# electric-skateboard-v2.net
KiCad netlist of a schematic drawn in EAGLE
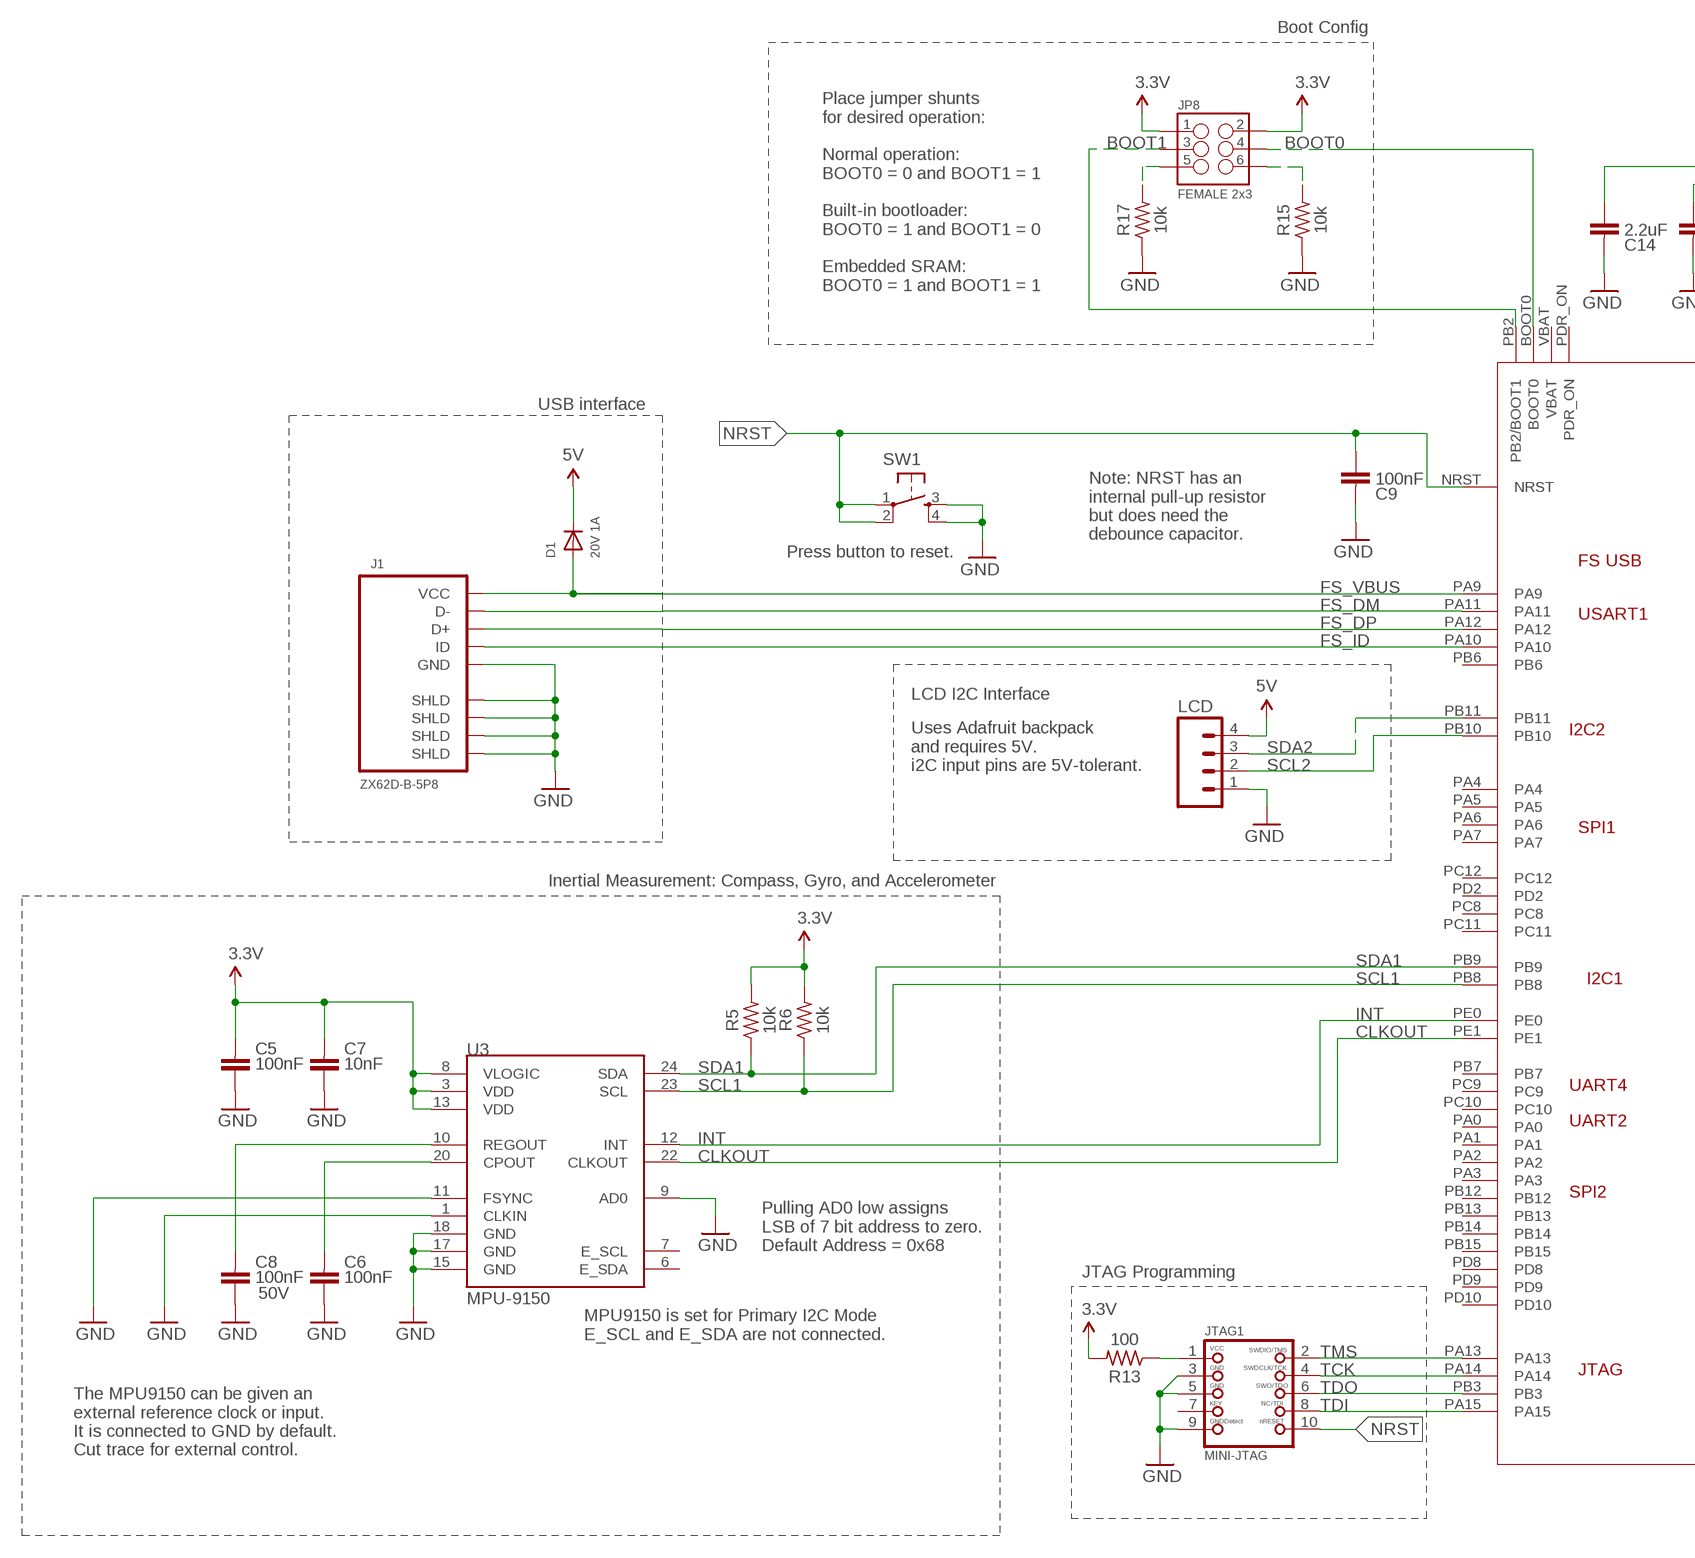
[diagram p0: schematic, sheet 1, part 1 of 2]
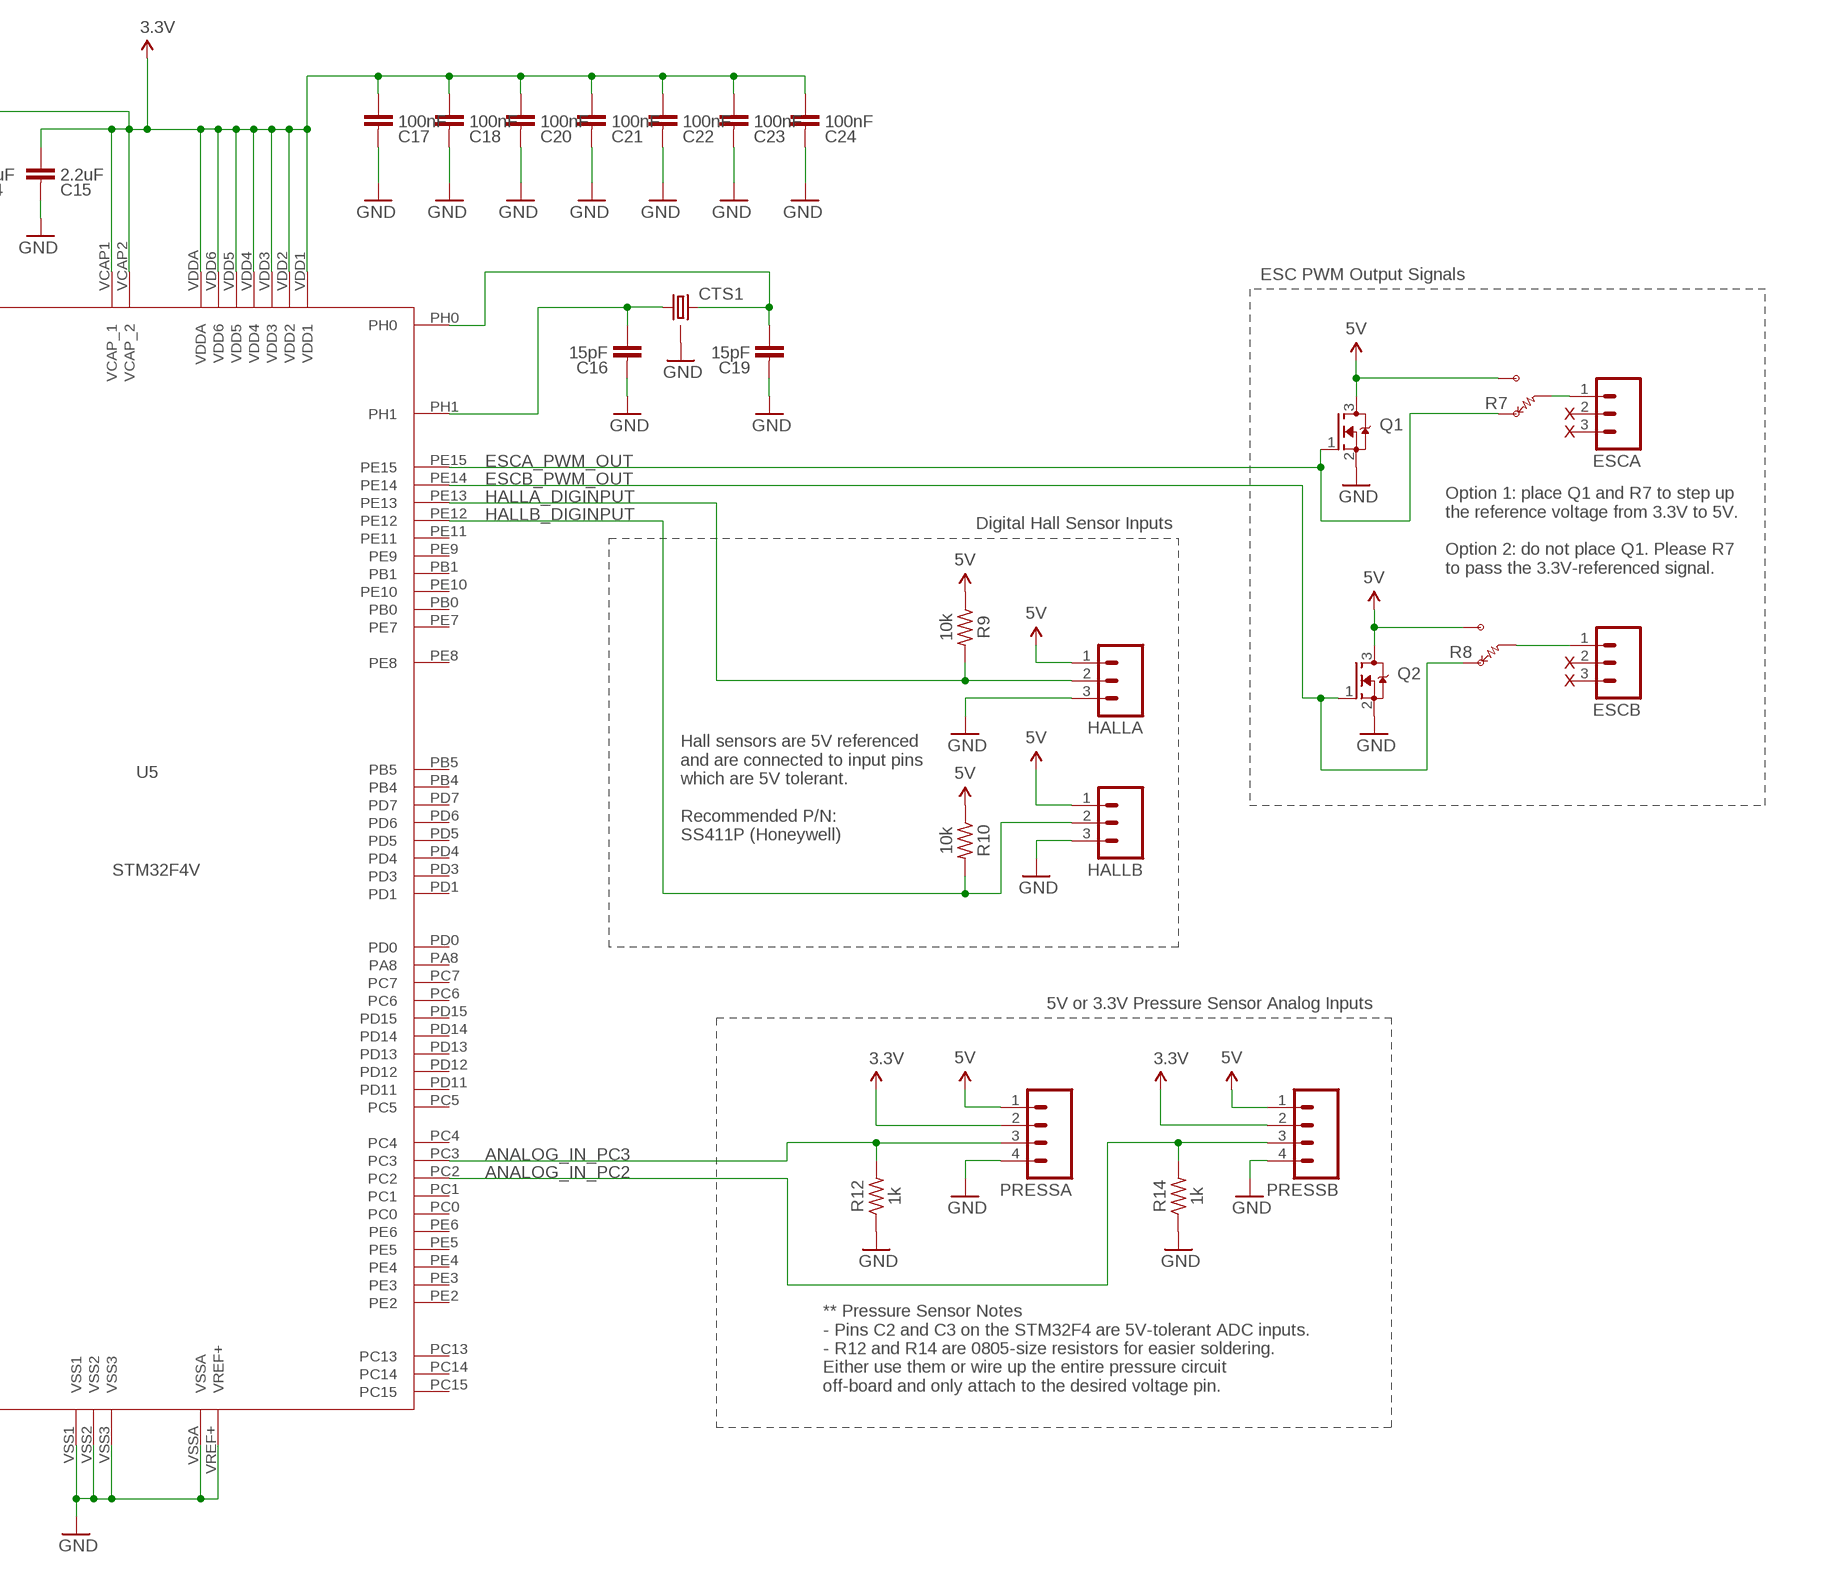
[diagram p1: schematic, sheet 1, part 2 of 2]
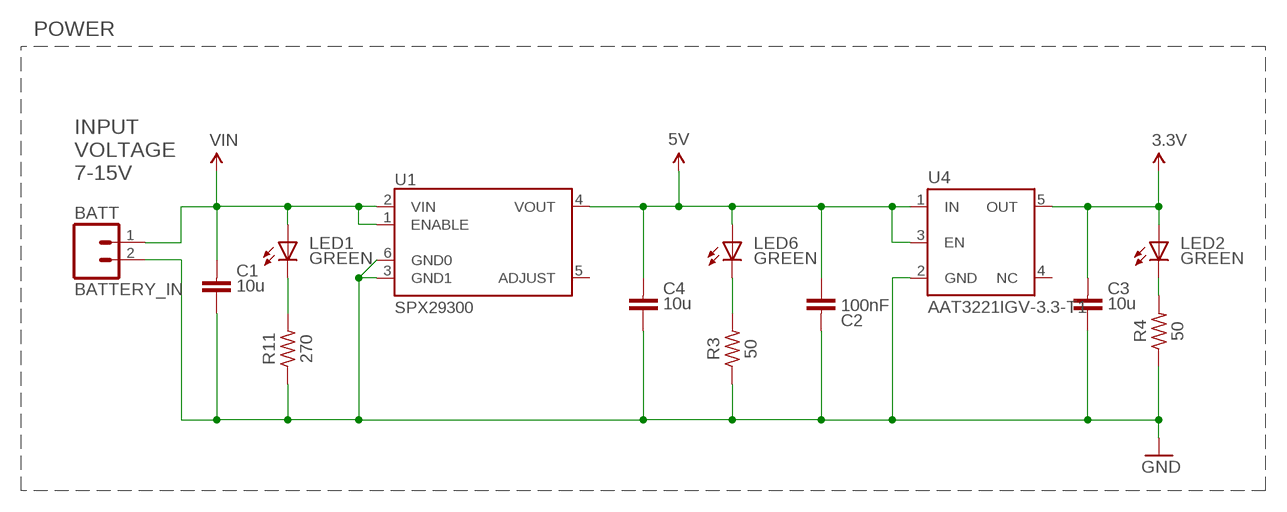
[diagram p2: schematic, sheet 2]

(export (version "E")
  (design (tool "Eeschema 10.0.6"))
  (components
    (comp (ref "BATTERY_IN")
      (value "BATT")
      (footprint "eagle-import:SCREWTERMINAL-5MM-2")
      (libsource (lib "eagle-import") (part "M025MM"))
    )
    (comp (ref "C1")
      (value "10u")
      (footprint "eagle-import:RLC-1210")
      (libsource (lib "eagle-import") (part "CAP-1210"))
    )
    (comp (ref "C2")
      (value "100nF")
      (footprint "eagle-import:RLC-0402")
      (libsource (lib "eagle-import") (part "CAP-0402"))
    )
    (comp (ref "C3")
      (value "10u")
      (footprint "eagle-import:RLC-1210")
      (libsource (lib "eagle-import") (part "CAP-1210"))
    )
    (comp (ref "C4")
      (value "10u")
      (footprint "eagle-import:RLC-1210")
      (libsource (lib "eagle-import") (part "CAP-1210"))
    )
    (comp (ref "LED1")
      (value "GREEN")
      (footprint "eagle-import:LED0603")
      (libsource (lib "eagle-import") (part "BG1111C"))
    )
    (comp (ref "LED2")
      (value "GREEN")
      (footprint "eagle-import:LED0603")
      (libsource (lib "eagle-import") (part "BG1111C"))
    )
    (comp (ref "LED6")
      (value "GREEN")
      (footprint "eagle-import:LED0603")
      (libsource (lib "eagle-import") (part "BG1111C"))
    )
    (comp (ref "R3")
      (value "50")
      (footprint "eagle-import:RLC-0402")
      (libsource (lib "eagle-import") (part "RES-0402"))
    )
    (comp (ref "R4")
      (value "50")
      (footprint "eagle-import:RLC-0402")
      (libsource (lib "eagle-import") (part "RES-0402"))
    )
    (comp (ref "R11")
      (value "270")
      (footprint "eagle-import:RLC-0402")
      (libsource (lib "eagle-import") (part "RES-0402"))
    )
    (comp (ref "U1")
      (value "SPX29300")
      (footprint "eagle-import:TO263-5")
      (libsource (lib "eagle-import") (part "VREG_TO263-5"))
    )
    (comp (ref "U4")
      (value "AAT3221IGV-3.3-T1")
      (footprint "eagle-import:SOT23-5")
      (libsource (lib "eagle-import") (part "INVERTER_SOT23-5"))
    )
    (comp (ref "C5")
      (value "100nF")
      (footprint "eagle-import:RLC-0402")
      (libsource (lib "eagle-import") (part "CAP-0402"))
    )
    (comp (ref "C6")
      (value "100nF")
      (footprint "eagle-import:RLC-0402")
      (libsource (lib "eagle-import") (part "CAP-0402"))
    )
    (comp (ref "C7")
      (value "10nF")
      (footprint "eagle-import:RLC-0402")
      (libsource (lib "eagle-import") (part "CAP-0402"))
    )
    (comp (ref "C8")
      (value "100nF")
      (footprint "eagle-import:RLC-0402")
      (libsource (lib "eagle-import") (part "CAP-0402"))
    )
    (comp (ref "C9")
      (value "100nF")
      (footprint "eagle-import:RLC-0402")
      (libsource (lib "eagle-import") (part "CAP-0402"))
    )
    (comp (ref "C14")
      (value "2.2uF")
      (footprint "eagle-import:RLC-0805")
      (libsource (lib "eagle-import") (part "CAP-0805"))
    )
    (comp (ref "C15")
      (value "2.2uF")
      (footprint "eagle-import:RLC-0805")
      (libsource (lib "eagle-import") (part "CAP-0805"))
    )
    (comp (ref "C16")
      (value "15pF")
      (footprint "eagle-import:RLC-0402")
      (libsource (lib "eagle-import") (part "CAP-0402"))
    )
    (comp (ref "C17")
      (value "100nF")
      (footprint "eagle-import:RLC-0402")
      (libsource (lib "eagle-import") (part "CAP-0402"))
    )
    (comp (ref "C18")
      (value "100nF")
      (footprint "eagle-import:RLC-0402")
      (libsource (lib "eagle-import") (part "CAP-0402"))
    )
    (comp (ref "C19")
      (value "15pF")
      (footprint "eagle-import:RLC-0402")
      (libsource (lib "eagle-import") (part "CAP-0402"))
    )
    (comp (ref "C20")
      (value "100nF")
      (footprint "eagle-import:RLC-0402")
      (libsource (lib "eagle-import") (part "CAP-0402"))
    )
    (comp (ref "C21")
      (value "100nF")
      (footprint "eagle-import:RLC-0402")
      (libsource (lib "eagle-import") (part "CAP-0402"))
    )
    (comp (ref "C22")
      (value "100nF")
      (footprint "eagle-import:RLC-0402")
      (libsource (lib "eagle-import") (part "CAP-0402"))
    )
    (comp (ref "C23")
      (value "100nF")
      (footprint "eagle-import:RLC-0402")
      (libsource (lib "eagle-import") (part "CAP-0402"))
    )
    (comp (ref "C24")
      (value "100nF")
      (footprint "eagle-import:RLC-0402")
      (libsource (lib "eagle-import") (part "CAP-0402"))
    )
    (comp (ref "CTS1")
      (value "CRYSTALCTS406")
      (footprint "eagle-import:CTS406")
      (libsource (lib "eagle-import") (part "CRYSTALCTS406"))
    )
    (comp (ref "D1")
      (value "20V 1A")
      (footprint "eagle-import:SMADIODE")
      (libsource (lib "eagle-import") (part "DIODESMA"))
    )
    (comp (ref "ESCA")
      (value "M03LOCK_LONGPADS")
      (footprint "eagle-import:1X03_LOCK_LONGPADS")
      (libsource (lib "eagle-import") (part "M03LOCK_LONGPADS"))
    )
    (comp (ref "ESCB")
      (value "M03LOCK_LONGPADS")
      (footprint "eagle-import:1X03_LOCK_LONGPADS")
      (libsource (lib "eagle-import") (part "M03LOCK_LONGPADS"))
    )
    (comp (ref "HALLA")
      (value "M03LOCK_LONGPADS")
      (footprint "eagle-import:1X03_LOCK_LONGPADS")
      (libsource (lib "eagle-import") (part "M03LOCK_LONGPADS"))
    )
    (comp (ref "HALLB")
      (value "M03LOCK_LONGPADS")
      (footprint "eagle-import:1X03_LOCK_LONGPADS")
      (libsource (lib "eagle-import") (part "M03LOCK_LONGPADS"))
    )
    (comp (ref "J1")
      (value "ZX62D-B-5P8")
      (footprint "eagle-import:ZX62D-B-5P8")
      (libsource (lib "eagle-import") (part "ZX62D-B-5P8"))
    )
    (comp (ref "JP8")
      (value "FEMALE 2x3")
      (footprint "eagle-import:2X3")
      (libsource (lib "eagle-import") (part "M03X2FEMALE"))
    )
    (comp (ref "JTAG1")
      (value "MINI-JTAG")
      (footprint "eagle-import:MICROBUILDER_2X05_1.27MM_SMT")
      (libsource (lib "eagle-import") (part "MICROBUILDER_JTAG-CORTEXM3"))
    )
    (comp (ref "LCD")
      (value "M04SCREW_LOCK")
      (footprint "eagle-import:SCREWTERMINAL-3.5MM-4_LOCK")
      (libsource (lib "eagle-import") (part "M04SCREW_LOCK"))
    )
    (comp (ref "PRESSA")
      (value "M04LOCK_LONGPADS")
      (footprint "eagle-import:1X04_LOCK_LONGPADS")
      (libsource (lib "eagle-import") (part "M04LOCK_LONGPADS"))
    )
    (comp (ref "PRESSB")
      (value "M04LOCK_LONGPADS")
      (footprint "eagle-import:1X04_LOCK_LONGPADS")
      (libsource (lib "eagle-import") (part "M04LOCK_LONGPADS"))
    )
    (comp (ref "Q1")
      (value "NTR4501N-D")
      (footprint "eagle-import:SOT-23")
      (libsource (lib "eagle-import") (part "NTR4501N-D"))
    )
    (comp (ref "Q2")
      (value "NTR4501N-D")
      (footprint "eagle-import:SOT-23")
      (libsource (lib "eagle-import") (part "NTR4501N-D"))
    )
    (comp (ref "R5")
      (value "10k")
      (footprint "eagle-import:RLC-0402")
      (libsource (lib "eagle-import") (part "RES-0402"))
    )
    (comp (ref "R6")
      (value "10k")
      (footprint "eagle-import:RLC-0402")
      (libsource (lib "eagle-import") (part "RES-0402"))
    )
    (comp (ref "R7")
      (value "RES-OPTION")
      (footprint "eagle-import:CAP-OPTION")
      (libsource (lib "eagle-import") (part "RES-OPTION"))
    )
    (comp (ref "R8")
      (value "RES-OPTION")
      (footprint "eagle-import:CAP-OPTION")
      (libsource (lib "eagle-import") (part "RES-OPTION"))
    )
    (comp (ref "R9")
      (value "10k")
      (footprint "eagle-import:RLC-0402")
      (libsource (lib "eagle-import") (part "RES-0402"))
    )
    (comp (ref "R10")
      (value "10k")
      (footprint "eagle-import:RLC-0402")
      (libsource (lib "eagle-import") (part "RES-0402"))
    )
    (comp (ref "R12")
      (value "1k")
      (footprint "eagle-import:RLC-0402")
      (libsource (lib "eagle-import") (part "RES-0402"))
    )
    (comp (ref "R13")
      (value "100")
      (footprint "eagle-import:RLC-0402")
      (libsource (lib "eagle-import") (part "RES-0402"))
    )
    (comp (ref "R14")
      (value "1k")
      (footprint "eagle-import:RLC-0402")
      (libsource (lib "eagle-import") (part "RES-0402"))
    )
    (comp (ref "R15")
      (value "10k")
      (footprint "eagle-import:RLC-0402")
      (libsource (lib "eagle-import") (part "RES-0402"))
    )
    (comp (ref "R17")
      (value "10k")
      (footprint "eagle-import:RLC-0402")
      (libsource (lib "eagle-import") (part "RES-0402"))
    )
    (comp (ref "SW1")
      (value "TACTILE-SWITCH-PTH")
      (footprint "eagle-import:TAC-SWITCH-PTH")
      (libsource (lib "eagle-import") (part "TACTILE-SWITCH-PTH"))
    )
    (comp (ref "U3")
      (value "MPU-9150")
      (footprint "eagle-import:QFN-24-NP")
      (libsource (lib "eagle-import") (part "MPU-9150QFN-24-NP"))
    )
    (comp (ref "U5")
      (value "STM32F4V")
      (footprint "eagle-import:STM32F4_LQFP100")
      (libsource (lib "eagle-import") (part "STM32F4_STM32F4V_100PIN_FOXCAR"))
    )
  )
  (nets
    (net (code "1") (name "3.3V") (class "Default")
      (node (ref "C14") (pin "2") (pinfunction "2_2") (pintype "passive"))
      (node (ref "C15") (pin "2") (pinfunction "2_2") (pintype "passive"))
      (node (ref "C17") (pin "2") (pinfunction "2_2") (pintype "passive"))
      (node (ref "C18") (pin "2") (pinfunction "2_2") (pintype "passive"))
      (node (ref "C20") (pin "2") (pinfunction "2_2") (pintype "passive"))
      (node (ref "C21") (pin "2") (pinfunction "2_2") (pintype "passive"))
      (node (ref "C22") (pin "2") (pinfunction "2_2") (pintype "passive"))
      (node (ref "C23") (pin "2") (pinfunction "2_2") (pintype "passive"))
      (node (ref "C24") (pin "2") (pinfunction "2_2") (pintype "passive"))
      (node (ref "C3") (pin "1") (pinfunction "1_1") (pintype "passive"))
      (node (ref "C5") (pin "1") (pinfunction "1_1") (pintype "passive"))
      (node (ref "C7") (pin "1") (pinfunction "1_1") (pintype "passive"))
      (node (ref "JP8") (pin "1") (pinfunction "1_1") (pintype "bidirectional"))
      (node (ref "JP8") (pin "2") (pinfunction "2_2") (pintype "bidirectional"))
      (node (ref "LED2") (pin "A") (pinfunction "A_A") (pintype "passive"))
      (node (ref "PRESSA") (pin "2") (pinfunction "2_2") (pintype "passive"))
      (node (ref "PRESSB") (pin "2") (pinfunction "2_2") (pintype "passive"))
      (node (ref "R13") (pin "2") (pinfunction "2_2") (pintype "passive"))
      (node (ref "R5") (pin "2") (pinfunction "2_2") (pintype "passive"))
      (node (ref "R6") (pin "2") (pinfunction "2_2") (pintype "passive"))
      (node (ref "U3") (pin "13") (pinfunction "VDD_13") (pintype "bidirectional"))
      (node (ref "U3") (pin "3") (pinfunction "VDD_3") (pintype "bidirectional"))
      (node (ref "U3") (pin "8") (pinfunction "VLOGIC_8") (pintype "bidirectional"))
      (node (ref "U4") (pin "5") (pinfunction "OUT_5") (pintype "bidirectional"))
      (node (ref "U5") (pin "VCAP1") (pinfunction "VCAP_1_VCAP1") (pintype "bidirectional"))
      (node (ref "U5") (pin "VCAP2") (pinfunction "VCAP_2_VCAP2") (pintype "bidirectional"))
      (node (ref "U5") (pin "VDD1") (pinfunction "VDD1_VDD1") (pintype "bidirectional"))
      (node (ref "U5") (pin "VDD2") (pinfunction "VDD2_VDD2") (pintype "bidirectional"))
      (node (ref "U5") (pin "VDD3") (pinfunction "VDD3_VDD3") (pintype "bidirectional"))
      (node (ref "U5") (pin "VDD4") (pinfunction "VDD4_VDD4") (pintype "bidirectional"))
      (node (ref "U5") (pin "VDD5") (pinfunction "VDD5_VDD5") (pintype "bidirectional"))
      (node (ref "U5") (pin "VDD6") (pinfunction "VDD6_VDD6") (pintype "bidirectional"))
      (node (ref "U5") (pin "VDDA") (pinfunction "VDDA_VDDA") (pintype "bidirectional"))
    )
    (net (code "2") (name "5V") (class "Default")
      (node (ref "C2") (pin "2") (pinfunction "2_2") (pintype "passive"))
      (node (ref "C4") (pin "1") (pinfunction "1_1") (pintype "passive"))
      (node (ref "D1") (pin "C") (pinfunction "C_C") (pintype "passive"))
      (node (ref "HALLA") (pin "1") (pinfunction "1_1") (pintype "passive"))
      (node (ref "HALLB") (pin "1") (pinfunction "1_1") (pintype "passive"))
      (node (ref "LCD") (pin "4") (pinfunction "4_4") (pintype "passive"))
      (node (ref "LED6") (pin "A") (pinfunction "A_A") (pintype "passive"))
      (node (ref "PRESSA") (pin "1") (pinfunction "1_1") (pintype "passive"))
      (node (ref "PRESSB") (pin "1") (pinfunction "1_1") (pintype "passive"))
      (node (ref "Q1") (pin "3") (pinfunction "D_3") (pintype "bidirectional"))
      (node (ref "Q2") (pin "3") (pinfunction "D_3") (pintype "bidirectional"))
      (node (ref "R10") (pin "1") (pinfunction "1_1") (pintype "passive"))
      (node (ref "R7") (pin "3") (pinfunction "3_3") (pintype "passive"))
      (node (ref "R8") (pin "3") (pinfunction "3_3") (pintype "passive"))
      (node (ref "R9") (pin "1") (pinfunction "1_1") (pintype "passive"))
      (node (ref "U1") (pin "4") (pinfunction "VOUT_4") (pintype "bidirectional"))
      (node (ref "U4") (pin "1") (pinfunction "IN_1") (pintype "bidirectional"))
      (node (ref "U4") (pin "3") (pinfunction "EN_3") (pintype "bidirectional"))
    )
    (net (code "3") (name "ANALOG_IN_PC2") (class "Default")
      (node (ref "PRESSB") (pin "3") (pinfunction "3_3") (pintype "passive"))
      (node (ref "R14") (pin "2") (pinfunction "2_2") (pintype "passive"))
      (node (ref "U5") (pin "PC2") (pinfunction "PC2_PC2") (pintype "bidirectional"))
    )
    (net (code "4") (name "ANALOG_IN_PC3") (class "Default")
      (node (ref "PRESSA") (pin "3") (pinfunction "3_3") (pintype "passive"))
      (node (ref "R12") (pin "2") (pinfunction "2_2") (pintype "passive"))
      (node (ref "U5") (pin "PC3") (pinfunction "PC3_PC3") (pintype "bidirectional"))
    )
    (net (code "5") (name "BOOT0") (class "Default")
      (node (ref "JP8") (pin "4") (pinfunction "4_4") (pintype "bidirectional"))
      (node (ref "U5") (pin "BOOT0") (pinfunction "BOOT0_BOOT0") (pintype "bidirectional"))
    )
    (net (code "6") (name "BOOT1") (class "Default")
      (node (ref "JP8") (pin "3") (pinfunction "3_3") (pintype "bidirectional"))
      (node (ref "U5") (pin "PB2") (pinfunction "PB2/BOOT1_PB2") (pintype "bidirectional"))
    )
    (net (code "7") (name "CLKOUT") (class "Default")
      (node (ref "U3") (pin "22") (pinfunction "CLKOUT_22") (pintype "bidirectional"))
      (node (ref "U5") (pin "PE1") (pinfunction "PE1_PE1") (pintype "bidirectional"))
    )
    (net (code "8") (name "ESCA_PWM_OUT") (class "Default")
      (node (ref "Q1") (pin "1") (pinfunction "G_1") (pintype "bidirectional"))
      (node (ref "R7") (pin "1") (pinfunction "1_1") (pintype "passive"))
      (node (ref "U5") (pin "PE15") (pinfunction "PE15_PE15") (pintype "bidirectional"))
    )
    (net (code "9") (name "ESCB_PWM_OUT") (class "Default")
      (node (ref "Q2") (pin "1") (pinfunction "G_1") (pintype "bidirectional"))
      (node (ref "R8") (pin "1") (pinfunction "1_1") (pintype "passive"))
      (node (ref "U5") (pin "PE14") (pinfunction "PE14_PE14") (pintype "bidirectional"))
    )
    (net (code "10") (name "FS_DM") (class "Default")
      (node (ref "J1") (pin "P2") (pinfunction "D-_P2") (pintype "bidirectional"))
      (node (ref "U5") (pin "PA11") (pinfunction "PA11_PA11") (pintype "bidirectional"))
    )
    (net (code "11") (name "FS_DP") (class "Default")
      (node (ref "J1") (pin "P3") (pinfunction "D+_P3") (pintype "bidirectional"))
      (node (ref "U5") (pin "PA12") (pinfunction "PA12_PA12") (pintype "bidirectional"))
    )
    (net (code "12") (name "FS_ID") (class "Default")
      (node (ref "J1") (pin "P4") (pinfunction "ID_P4") (pintype "bidirectional"))
      (node (ref "U5") (pin "PA10") (pinfunction "PA10_PA10") (pintype "bidirectional"))
    )
    (net (code "13") (name "FS_VBUS") (class "Default")
      (node (ref "D1") (pin "A") (pinfunction "A_A") (pintype "passive"))
      (node (ref "J1") (pin "P1") (pinfunction "VCC_P1") (pintype "power_in"))
      (node (ref "U5") (pin "PA9") (pinfunction "PA9_PA9") (pintype "bidirectional"))
    )
    (net (code "14") (name "GND") (class "Default")
      (node (ref "BATTERY_IN") (pin "2") (pinfunction "2_2") (pintype "passive"))
      (node (ref "C1") (pin "2") (pinfunction "2_2") (pintype "passive"))
      (node (ref "C14") (pin "1") (pinfunction "1_1") (pintype "passive"))
      (node (ref "C15") (pin "1") (pinfunction "1_1") (pintype "passive"))
      (node (ref "C16") (pin "1") (pinfunction "1_1") (pintype "passive"))
      (node (ref "C17") (pin "1") (pinfunction "1_1") (pintype "passive"))
      (node (ref "C18") (pin "1") (pinfunction "1_1") (pintype "passive"))
      (node (ref "C19") (pin "1") (pinfunction "1_1") (pintype "passive"))
      (node (ref "C2") (pin "1") (pinfunction "1_1") (pintype "passive"))
      (node (ref "C20") (pin "1") (pinfunction "1_1") (pintype "passive"))
      (node (ref "C21") (pin "1") (pinfunction "1_1") (pintype "passive"))
      (node (ref "C22") (pin "1") (pinfunction "1_1") (pintype "passive"))
      (node (ref "C23") (pin "1") (pinfunction "1_1") (pintype "passive"))
      (node (ref "C24") (pin "1") (pinfunction "1_1") (pintype "passive"))
      (node (ref "C3") (pin "2") (pinfunction "2_2") (pintype "passive"))
      (node (ref "C4") (pin "2") (pinfunction "2_2") (pintype "passive"))
      (node (ref "C5") (pin "2") (pinfunction "2_2") (pintype "passive"))
      (node (ref "C6") (pin "2") (pinfunction "2_2") (pintype "passive"))
      (node (ref "C7") (pin "2") (pinfunction "2_2") (pintype "passive"))
      (node (ref "C8") (pin "2") (pinfunction "2_2") (pintype "passive"))
      (node (ref "C9") (pin "1") (pinfunction "1_1") (pintype "passive"))
      (node (ref "CTS1") (pin "2") (pinfunction "GND_2") (pintype "power_in"))
      (node (ref "CTS1") (pin "4") (pinfunction "GND_4") (pintype "power_in"))
      (node (ref "HALLA") (pin "3") (pinfunction "3_3") (pintype "passive"))
      (node (ref "HALLB") (pin "3") (pinfunction "3_3") (pintype "passive"))
      (node (ref "J1") (pin "P$1") (pinfunction "SHLD_P$1") (pintype "power_in"))
      (node (ref "J1") (pin "P$2") (pinfunction "SHLD_P$2") (pintype "power_in"))
      (node (ref "J1") (pin "P$3") (pinfunction "SHLD_P$3") (pintype "power_in"))
      (node (ref "J1") (pin "P$4") (pinfunction "SHLD_P$4") (pintype "power_in"))
      (node (ref "J1") (pin "P5") (pinfunction "GND_P5") (pintype "power_in"))
      (node (ref "JTAG1") (pin "3") (pinfunction "3_3") (pintype "passive"))
      (node (ref "JTAG1") (pin "5") (pinfunction "5_5") (pintype "passive"))
      (node (ref "JTAG1") (pin "9") (pinfunction "9_9") (pintype "passive"))
      (node (ref "LCD") (pin "1") (pinfunction "1_1") (pintype "passive"))
      (node (ref "PRESSA") (pin "4") (pinfunction "4_4") (pintype "passive"))
      (node (ref "PRESSB") (pin "4") (pinfunction "4_4") (pintype "passive"))
      (node (ref "Q1") (pin "2") (pinfunction "S_2") (pintype "bidirectional"))
      (node (ref "Q2") (pin "2") (pinfunction "S_2") (pintype "bidirectional"))
      (node (ref "R11") (pin "1") (pinfunction "1_1") (pintype "passive"))
      (node (ref "R12") (pin "1") (pinfunction "1_1") (pintype "passive"))
      (node (ref "R14") (pin "1") (pinfunction "1_1") (pintype "passive"))
      (node (ref "R15") (pin "1") (pinfunction "1_1") (pintype "passive"))
      (node (ref "R17") (pin "1") (pinfunction "1_1") (pintype "passive"))
      (node (ref "R3") (pin "1") (pinfunction "1_1") (pintype "passive"))
      (node (ref "R4") (pin "1") (pinfunction "1_1") (pintype "passive"))
      (node (ref "SW1") (pin "3") (pinfunction "3_3") (pintype "passive"))
      (node (ref "SW1") (pin "4") (pinfunction "4_4") (pintype "passive"))
      (node (ref "U1") (pin "3") (pinfunction "GND1_3") (pintype "bidirectional"))
      (node (ref "U1") (pin "6") (pinfunction "GND0_6") (pintype "bidirectional"))
      (node (ref "U3") (pin "1") (pinfunction "CLKIN_1") (pintype "bidirectional"))
      (node (ref "U3") (pin "11") (pinfunction "FSYNC_11") (pintype "bidirectional"))
      (node (ref "U3") (pin "15") (pinfunction "GND_15") (pintype "bidirectional"))
      (node (ref "U3") (pin "17") (pinfunction "GND_17") (pintype "bidirectional"))
      (node (ref "U3") (pin "18") (pinfunction "GND_18") (pintype "bidirectional"))
      (node (ref "U3") (pin "9") (pinfunction "AD0_9") (pintype "bidirectional"))
      (node (ref "U4") (pin "2") (pinfunction "GND_2") (pintype "bidirectional"))
      (node (ref "U5") (pin "VREF+") (pinfunction "VREF+_VREF+") (pintype "bidirectional"))
      (node (ref "U5") (pin "VSS1") (pinfunction "VSS1_VSS1") (pintype "bidirectional"))
      (node (ref "U5") (pin "VSS2") (pinfunction "VSS2_VSS2") (pintype "bidirectional"))
      (node (ref "U5") (pin "VSS3") (pinfunction "VSS3_VSS3") (pintype "bidirectional"))
      (node (ref "U5") (pin "VSSA") (pinfunction "VSSA_VSSA") (pintype "bidirectional"))
    )
    (net (code "15") (name "HALLA_DIGINPUT") (class "Default")
      (node (ref "HALLA") (pin "2") (pinfunction "2_2") (pintype "passive"))
      (node (ref "R9") (pin "2") (pinfunction "2_2") (pintype "passive"))
      (node (ref "U5") (pin "PE13") (pinfunction "PE13_PE13") (pintype "bidirectional"))
    )
    (net (code "16") (name "HALLB_DIGINPUT") (class "Default")
      (node (ref "HALLB") (pin "2") (pinfunction "2_2") (pintype "passive"))
      (node (ref "R10") (pin "2") (pinfunction "2_2") (pintype "passive"))
      (node (ref "U5") (pin "PE12") (pinfunction "PE12_PE12") (pintype "bidirectional"))
    )
    (net (code "17") (name "INT") (class "Default")
      (node (ref "U3") (pin "12") (pinfunction "INT_12") (pintype "bidirectional"))
      (node (ref "U5") (pin "PE0") (pinfunction "PE0_PE0") (pintype "bidirectional"))
    )
    (net (code "18") (name "NRST") (class "Default")
      (node (ref "C9") (pin "2") (pinfunction "2_2") (pintype "passive"))
      (node (ref "JTAG1") (pin "10") (pinfunction "10_10") (pintype "passive"))
      (node (ref "SW1") (pin "1") (pinfunction "1_1") (pintype "passive"))
      (node (ref "SW1") (pin "2") (pinfunction "2_2") (pintype "passive"))
      (node (ref "U5") (pin "NRST") (pinfunction "NRST_NRST") (pintype "bidirectional"))
    )
    (net (code "19") (name "Net-(C16-Pad2)") (class "Default")
      (node (ref "C16") (pin "2") (pinfunction "2_2") (pintype "passive"))
      (node (ref "CTS1") (pin "1") (pinfunction "1_1") (pintype "passive"))
      (node (ref "U5") (pin "PH1") (pinfunction "PH1_PH1") (pintype "bidirectional"))
    )
    (net (code "20") (name "Net-(CTS1-2)") (class "Default")
      (node (ref "C19") (pin "2") (pinfunction "2_2") (pintype "passive"))
      (node (ref "CTS1") (pin "3") (pinfunction "2_3") (pintype "passive"))
      (node (ref "U5") (pin "PH0") (pinfunction "PH0_PH0") (pintype "bidirectional"))
    )
    (net (code "21") (name "Net-(ESCA-Pad1)") (class "Default")
      (node (ref "ESCA") (pin "1") (pinfunction "1_1") (pintype "passive"))
      (node (ref "R7") (pin "2") (pinfunction "2_2") (pintype "passive"))
    )
    (net (code "22") (name "Net-(ESCB-Pad1)") (class "Default")
      (node (ref "ESCB") (pin "1") (pinfunction "1_1") (pintype "passive"))
      (node (ref "R8") (pin "2") (pinfunction "2_2") (pintype "passive"))
    )
    (net (code "23") (name "Net-(JP8-Pad5)") (class "Default")
      (node (ref "JP8") (pin "5") (pinfunction "5_5") (pintype "bidirectional"))
      (node (ref "R17") (pin "2") (pinfunction "2_2") (pintype "passive"))
    )
    (net (code "24") (name "Net-(JP8-Pad6)") (class "Default")
      (node (ref "JP8") (pin "6") (pinfunction "6_6") (pintype "bidirectional"))
      (node (ref "R15") (pin "2") (pinfunction "2_2") (pintype "passive"))
    )
    (net (code "25") (name "Net-(JTAG1-Pad1)") (class "Default")
      (node (ref "JTAG1") (pin "1") (pinfunction "1_1") (pintype "passive"))
      (node (ref "R13") (pin "1") (pinfunction "1_1") (pintype "passive"))
    )
    (net (code "26") (name "Net-(LED1-PadC)") (class "Default")
      (node (ref "LED1") (pin "C") (pinfunction "C_C") (pintype "passive"))
      (node (ref "R11") (pin "2") (pinfunction "2_2") (pintype "passive"))
    )
    (net (code "27") (name "Net-(LED2-PadC)") (class "Default")
      (node (ref "LED2") (pin "C") (pinfunction "C_C") (pintype "passive"))
      (node (ref "R4") (pin "2") (pinfunction "2_2") (pintype "passive"))
    )
    (net (code "28") (name "Net-(LED6-PadC)") (class "Default")
      (node (ref "LED6") (pin "C") (pinfunction "C_C") (pintype "passive"))
      (node (ref "R3") (pin "2") (pinfunction "2_2") (pintype "passive"))
    )
    (net (code "29") (name "Net-(U3-CPOUT)") (class "Default")
      (node (ref "C6") (pin "1") (pinfunction "1_1") (pintype "passive"))
      (node (ref "U3") (pin "20") (pinfunction "CPOUT_20") (pintype "bidirectional"))
    )
    (net (code "30") (name "Net-(U3-REGOUT)") (class "Default")
      (node (ref "C8") (pin "1") (pinfunction "1_1") (pintype "passive"))
      (node (ref "U3") (pin "10") (pinfunction "REGOUT_10") (pintype "bidirectional"))
    )
    (net (code "31") (name "SCL1") (class "Default")
      (node (ref "R6") (pin "1") (pinfunction "1_1") (pintype "passive"))
      (node (ref "U3") (pin "23") (pinfunction "SCL_23") (pintype "bidirectional"))
      (node (ref "U5") (pin "PB8") (pinfunction "PB8_PB8") (pintype "bidirectional"))
    )
    (net (code "32") (name "SCL2") (class "Default")
      (node (ref "LCD") (pin "2") (pinfunction "2_2") (pintype "passive"))
      (node (ref "U5") (pin "PB10") (pinfunction "PB10_PB10") (pintype "bidirectional"))
    )
    (net (code "33") (name "SDA1") (class "Default")
      (node (ref "R5") (pin "1") (pinfunction "1_1") (pintype "passive"))
      (node (ref "U3") (pin "24") (pinfunction "SDA_24") (pintype "bidirectional"))
      (node (ref "U5") (pin "PB9") (pinfunction "PB9_PB9") (pintype "bidirectional"))
    )
    (net (code "34") (name "SDA2") (class "Default")
      (node (ref "LCD") (pin "3") (pinfunction "3_3") (pintype "passive"))
      (node (ref "U5") (pin "PB11") (pinfunction "PB11_PB11") (pintype "bidirectional"))
    )
    (net (code "35") (name "TCK") (class "Default")
      (node (ref "JTAG1") (pin "4") (pinfunction "4_4") (pintype "passive"))
      (node (ref "U5") (pin "PA14") (pinfunction "PA14_PA14") (pintype "bidirectional"))
    )
    (net (code "36") (name "TDI") (class "Default")
      (node (ref "JTAG1") (pin "8") (pinfunction "8_8") (pintype "passive"))
      (node (ref "U5") (pin "PA15") (pinfunction "PA15_PA15") (pintype "bidirectional"))
    )
    (net (code "37") (name "TDO") (class "Default")
      (node (ref "JTAG1") (pin "6") (pinfunction "6_6") (pintype "passive"))
      (node (ref "U5") (pin "PB3") (pinfunction "PB3_PB3") (pintype "bidirectional"))
    )
    (net (code "38") (name "TMS") (class "Default")
      (node (ref "JTAG1") (pin "2") (pinfunction "2_2") (pintype "passive"))
      (node (ref "U5") (pin "PA13") (pinfunction "PA13_PA13") (pintype "bidirectional"))
    )
    (net (code "39") (name "VIN") (class "Default")
      (node (ref "BATTERY_IN") (pin "1") (pinfunction "1_1") (pintype "passive"))
      (node (ref "C1") (pin "1") (pinfunction "1_1") (pintype "passive"))
      (node (ref "LED1") (pin "A") (pinfunction "A_A") (pintype "passive"))
      (node (ref "U1") (pin "1") (pinfunction "ENABLE_1") (pintype "bidirectional"))
      (node (ref "U1") (pin "2") (pinfunction "VIN_2") (pintype "bidirectional"))
    )
    (net (code "40") (name "unconnected-(ESCA-Pad2)") (class "Default")
      (node (ref "ESCA") (pin "2") (pinfunction "2_2") (pintype "passive"))
    )
    (net (code "41") (name "unconnected-(ESCA-Pad3)") (class "Default")
      (node (ref "ESCA") (pin "3") (pinfunction "3_3") (pintype "passive"))
    )
    (net (code "42") (name "unconnected-(ESCB-Pad2)") (class "Default")
      (node (ref "ESCB") (pin "2") (pinfunction "2_2") (pintype "passive"))
    )
    (net (code "43") (name "unconnected-(ESCB-Pad3)") (class "Default")
      (node (ref "ESCB") (pin "3") (pinfunction "3_3") (pintype "passive"))
    )
    (net (code "44") (name "unconnected-(JTAG1-Pad7)") (class "Default")
      (node (ref "JTAG1") (pin "7") (pinfunction "7_7") (pintype "passive"))
    )
    (net (code "45") (name "unconnected-(U1-ADJUST-Pad5)") (class "Default")
      (node (ref "U1") (pin "5") (pinfunction "ADJUST_5") (pintype "bidirectional"))
    )
    (net (code "46") (name "unconnected-(U3-E_SCL-Pad7)") (class "Default")
      (node (ref "U3") (pin "7") (pinfunction "E_SCL_7") (pintype "bidirectional"))
    )
    (net (code "47") (name "unconnected-(U3-E_SDA-Pad6)") (class "Default")
      (node (ref "U3") (pin "6") (pinfunction "E_SDA_6") (pintype "bidirectional"))
    )
    (net (code "48") (name "unconnected-(U4-NC-Pad4)") (class "Default")
      (node (ref "U4") (pin "4") (pinfunction "NC_4") (pintype "bidirectional"))
    )
    (net (code "49") (name "unconnected-(U5-PadPA0)") (class "Default")
      (node (ref "U5") (pin "PA0") (pinfunction "PA0_PA0") (pintype "bidirectional"))
    )
    (net (code "50") (name "unconnected-(U5-PadPA1)") (class "Default")
      (node (ref "U5") (pin "PA1") (pinfunction "PA1_PA1") (pintype "bidirectional"))
    )
    (net (code "51") (name "unconnected-(U5-PadPA2)") (class "Default")
      (node (ref "U5") (pin "PA2") (pinfunction "PA2_PA2") (pintype "bidirectional"))
    )
    (net (code "52") (name "unconnected-(U5-PadPA3)") (class "Default")
      (node (ref "U5") (pin "PA3") (pinfunction "PA3_PA3") (pintype "bidirectional"))
    )
    (net (code "53") (name "unconnected-(U5-PadPA4)") (class "Default")
      (node (ref "U5") (pin "PA4") (pinfunction "PA4_PA4") (pintype "bidirectional"))
    )
    (net (code "54") (name "unconnected-(U5-PadPA5)") (class "Default")
      (node (ref "U5") (pin "PA5") (pinfunction "PA5_PA5") (pintype "bidirectional"))
    )
    (net (code "55") (name "unconnected-(U5-PadPA6)") (class "Default")
      (node (ref "U5") (pin "PA6") (pinfunction "PA6_PA6") (pintype "bidirectional"))
    )
    (net (code "56") (name "unconnected-(U5-PadPA7)") (class "Default")
      (node (ref "U5") (pin "PA7") (pinfunction "PA7_PA7") (pintype "bidirectional"))
    )
    (net (code "57") (name "unconnected-(U5-PadPA8)") (class "Default")
      (node (ref "U5") (pin "PA8") (pinfunction "PA8_PA8") (pintype "bidirectional"))
    )
    (net (code "58") (name "unconnected-(U5-PadPB0)") (class "Default")
      (node (ref "U5") (pin "PB0") (pinfunction "PB0_PB0") (pintype "bidirectional"))
    )
    (net (code "59") (name "unconnected-(U5-PadPB1)") (class "Default")
      (node (ref "U5") (pin "PB1") (pinfunction "PB1_PB1") (pintype "bidirectional"))
    )
    (net (code "60") (name "unconnected-(U5-PadPB4)") (class "Default")
      (node (ref "U5") (pin "PB4") (pinfunction "PB4_PB4") (pintype "bidirectional"))
    )
    (net (code "61") (name "unconnected-(U5-PadPB5)") (class "Default")
      (node (ref "U5") (pin "PB5") (pinfunction "PB5_PB5") (pintype "bidirectional"))
    )
    (net (code "62") (name "unconnected-(U5-PadPB6)") (class "Default")
      (node (ref "U5") (pin "PB6") (pinfunction "PB6_PB6") (pintype "bidirectional"))
    )
    (net (code "63") (name "unconnected-(U5-PadPB7)") (class "Default")
      (node (ref "U5") (pin "PB7") (pinfunction "PB7_PB7") (pintype "bidirectional"))
    )
    (net (code "64") (name "unconnected-(U5-PadPB12)") (class "Default")
      (node (ref "U5") (pin "PB12") (pinfunction "PB12_PB12") (pintype "bidirectional"))
    )
    (net (code "65") (name "unconnected-(U5-PadPB13)") (class "Default")
      (node (ref "U5") (pin "PB13") (pinfunction "PB13_PB13") (pintype "bidirectional"))
    )
    (net (code "66") (name "unconnected-(U5-PadPB14)") (class "Default")
      (node (ref "U5") (pin "PB14") (pinfunction "PB14_PB14") (pintype "bidirectional"))
    )
    (net (code "67") (name "unconnected-(U5-PadPB15)") (class "Default")
      (node (ref "U5") (pin "PB15") (pinfunction "PB15_PB15") (pintype "bidirectional"))
    )
    (net (code "68") (name "unconnected-(U5-PadPC0)") (class "Default")
      (node (ref "U5") (pin "PC0") (pinfunction "PC0_PC0") (pintype "bidirectional"))
    )
    (net (code "69") (name "unconnected-(U5-PadPC1)") (class "Default")
      (node (ref "U5") (pin "PC1") (pinfunction "PC1_PC1") (pintype "bidirectional"))
    )
    (net (code "70") (name "unconnected-(U5-PadPC4)") (class "Default")
      (node (ref "U5") (pin "PC4") (pinfunction "PC4_PC4") (pintype "bidirectional"))
    )
    (net (code "71") (name "unconnected-(U5-PadPC5)") (class "Default")
      (node (ref "U5") (pin "PC5") (pinfunction "PC5_PC5") (pintype "bidirectional"))
    )
    (net (code "72") (name "unconnected-(U5-PadPC6)") (class "Default")
      (node (ref "U5") (pin "PC6") (pinfunction "PC6_PC6") (pintype "bidirectional"))
    )
    (net (code "73") (name "unconnected-(U5-PadPC7)") (class "Default")
      (node (ref "U5") (pin "PC7") (pinfunction "PC7_PC7") (pintype "bidirectional"))
    )
    (net (code "74") (name "unconnected-(U5-PadPC8)") (class "Default")
      (node (ref "U5") (pin "PC8") (pinfunction "PC8_PC8") (pintype "bidirectional"))
    )
    (net (code "75") (name "unconnected-(U5-PadPC9)") (class "Default")
      (node (ref "U5") (pin "PC9") (pinfunction "PC9_PC9") (pintype "bidirectional"))
    )
    (net (code "76") (name "unconnected-(U5-PadPC10)") (class "Default")
      (node (ref "U5") (pin "PC10") (pinfunction "PC10_PC10") (pintype "bidirectional"))
    )
    (net (code "77") (name "unconnected-(U5-PadPC11)") (class "Default")
      (node (ref "U5") (pin "PC11") (pinfunction "PC11_PC11") (pintype "bidirectional"))
    )
    (net (code "78") (name "unconnected-(U5-PadPC12)") (class "Default")
      (node (ref "U5") (pin "PC12") (pinfunction "PC12_PC12") (pintype "bidirectional"))
    )
    (net (code "79") (name "unconnected-(U5-PadPC13)") (class "Default")
      (node (ref "U5") (pin "PC13") (pinfunction "PC13_PC13") (pintype "bidirectional"))
    )
    (net (code "80") (name "unconnected-(U5-PadPC14)") (class "Default")
      (node (ref "U5") (pin "PC14") (pinfunction "PC14_PC14") (pintype "bidirectional"))
    )
    (net (code "81") (name "unconnected-(U5-PadPC15)") (class "Default")
      (node (ref "U5") (pin "PC15") (pinfunction "PC15_PC15") (pintype "bidirectional"))
    )
    (net (code "82") (name "unconnected-(U5-PadPD0)") (class "Default")
      (node (ref "U5") (pin "PD0") (pinfunction "PD0_PD0") (pintype "bidirectional"))
    )
    (net (code "83") (name "unconnected-(U5-PadPD1)") (class "Default")
      (node (ref "U5") (pin "PD1") (pinfunction "PD1_PD1") (pintype "bidirectional"))
    )
    (net (code "84") (name "unconnected-(U5-PadPD2)") (class "Default")
      (node (ref "U5") (pin "PD2") (pinfunction "PD2_PD2") (pintype "bidirectional"))
    )
    (net (code "85") (name "unconnected-(U5-PadPD3)") (class "Default")
      (node (ref "U5") (pin "PD3") (pinfunction "PD3_PD3") (pintype "bidirectional"))
    )
    (net (code "86") (name "unconnected-(U5-PadPD4)") (class "Default")
      (node (ref "U5") (pin "PD4") (pinfunction "PD4_PD4") (pintype "bidirectional"))
    )
    (net (code "87") (name "unconnected-(U5-PadPD5)") (class "Default")
      (node (ref "U5") (pin "PD5") (pinfunction "PD5_PD5") (pintype "bidirectional"))
    )
    (net (code "88") (name "unconnected-(U5-PadPD6)") (class "Default")
      (node (ref "U5") (pin "PD6") (pinfunction "PD6_PD6") (pintype "bidirectional"))
    )
    (net (code "89") (name "unconnected-(U5-PadPD7)") (class "Default")
      (node (ref "U5") (pin "PD7") (pinfunction "PD7_PD7") (pintype "bidirectional"))
    )
    (net (code "90") (name "unconnected-(U5-PadPD8)") (class "Default")
      (node (ref "U5") (pin "PD8") (pinfunction "PD8_PD8") (pintype "bidirectional"))
    )
    (net (code "91") (name "unconnected-(U5-PadPD9)") (class "Default")
      (node (ref "U5") (pin "PD9") (pinfunction "PD9_PD9") (pintype "bidirectional"))
    )
    (net (code "92") (name "unconnected-(U5-PadPD10)") (class "Default")
      (node (ref "U5") (pin "PD10") (pinfunction "PD10_PD10") (pintype "bidirectional"))
    )
    (net (code "93") (name "unconnected-(U5-PadPD11)") (class "Default")
      (node (ref "U5") (pin "PD11") (pinfunction "PD11_PD11") (pintype "bidirectional"))
    )
    (net (code "94") (name "unconnected-(U5-PadPD12)") (class "Default")
      (node (ref "U5") (pin "PD12") (pinfunction "PD12_PD12") (pintype "bidirectional"))
    )
    (net (code "95") (name "unconnected-(U5-PadPD13)") (class "Default")
      (node (ref "U5") (pin "PD13") (pinfunction "PD13_PD13") (pintype "bidirectional"))
    )
    (net (code "96") (name "unconnected-(U5-PadPD14)") (class "Default")
      (node (ref "U5") (pin "PD14") (pinfunction "PD14_PD14") (pintype "bidirectional"))
    )
    (net (code "97") (name "unconnected-(U5-PadPD15)") (class "Default")
      (node (ref "U5") (pin "PD15") (pinfunction "PD15_PD15") (pintype "bidirectional"))
    )
    (net (code "98") (name "unconnected-(U5-PadPDR_ON)") (class "Default")
      (node (ref "U5") (pin "PDR_ON") (pinfunction "PDR_ON_PDR_ON") (pintype "bidirectional"))
    )
    (net (code "99") (name "unconnected-(U5-PadPE2)") (class "Default")
      (node (ref "U5") (pin "PE2") (pinfunction "PE2_PE2") (pintype "bidirectional"))
    )
    (net (code "100") (name "unconnected-(U5-PadPE3)") (class "Default")
      (node (ref "U5") (pin "PE3") (pinfunction "PE3_PE3") (pintype "bidirectional"))
    )
    (net (code "101") (name "unconnected-(U5-PadPE4)") (class "Default")
      (node (ref "U5") (pin "PE4") (pinfunction "PE4_PE4") (pintype "bidirectional"))
    )
    (net (code "102") (name "unconnected-(U5-PadPE5)") (class "Default")
      (node (ref "U5") (pin "PE5") (pinfunction "PE5_PE5") (pintype "bidirectional"))
    )
    (net (code "103") (name "unconnected-(U5-PadPE6)") (class "Default")
      (node (ref "U5") (pin "PE6") (pinfunction "PE6_PE6") (pintype "bidirectional"))
    )
    (net (code "104") (name "unconnected-(U5-PadPE7)") (class "Default")
      (node (ref "U5") (pin "PE7") (pinfunction "PE7_PE7") (pintype "bidirectional"))
    )
    (net (code "105") (name "unconnected-(U5-PadPE8)") (class "Default")
      (node (ref "U5") (pin "PE8") (pinfunction "PE8_PE8") (pintype "bidirectional"))
    )
    (net (code "106") (name "unconnected-(U5-PadPE9)") (class "Default")
      (node (ref "U5") (pin "PE9") (pinfunction "PE9_PE9") (pintype "bidirectional"))
    )
    (net (code "107") (name "unconnected-(U5-PadPE10)") (class "Default")
      (node (ref "U5") (pin "PE10") (pinfunction "PE10_PE10") (pintype "bidirectional"))
    )
    (net (code "108") (name "unconnected-(U5-PadPE11)") (class "Default")
      (node (ref "U5") (pin "PE11") (pinfunction "PE11_PE11") (pintype "bidirectional"))
    )
    (net (code "109") (name "unconnected-(U5-PadVBAT)") (class "Default")
      (node (ref "U5") (pin "VBAT") (pinfunction "VBAT_VBAT") (pintype "bidirectional"))
    )
  )
)
